# MiniWhipNext.net
KiCad netlist of a schematic drawn in EAGLE
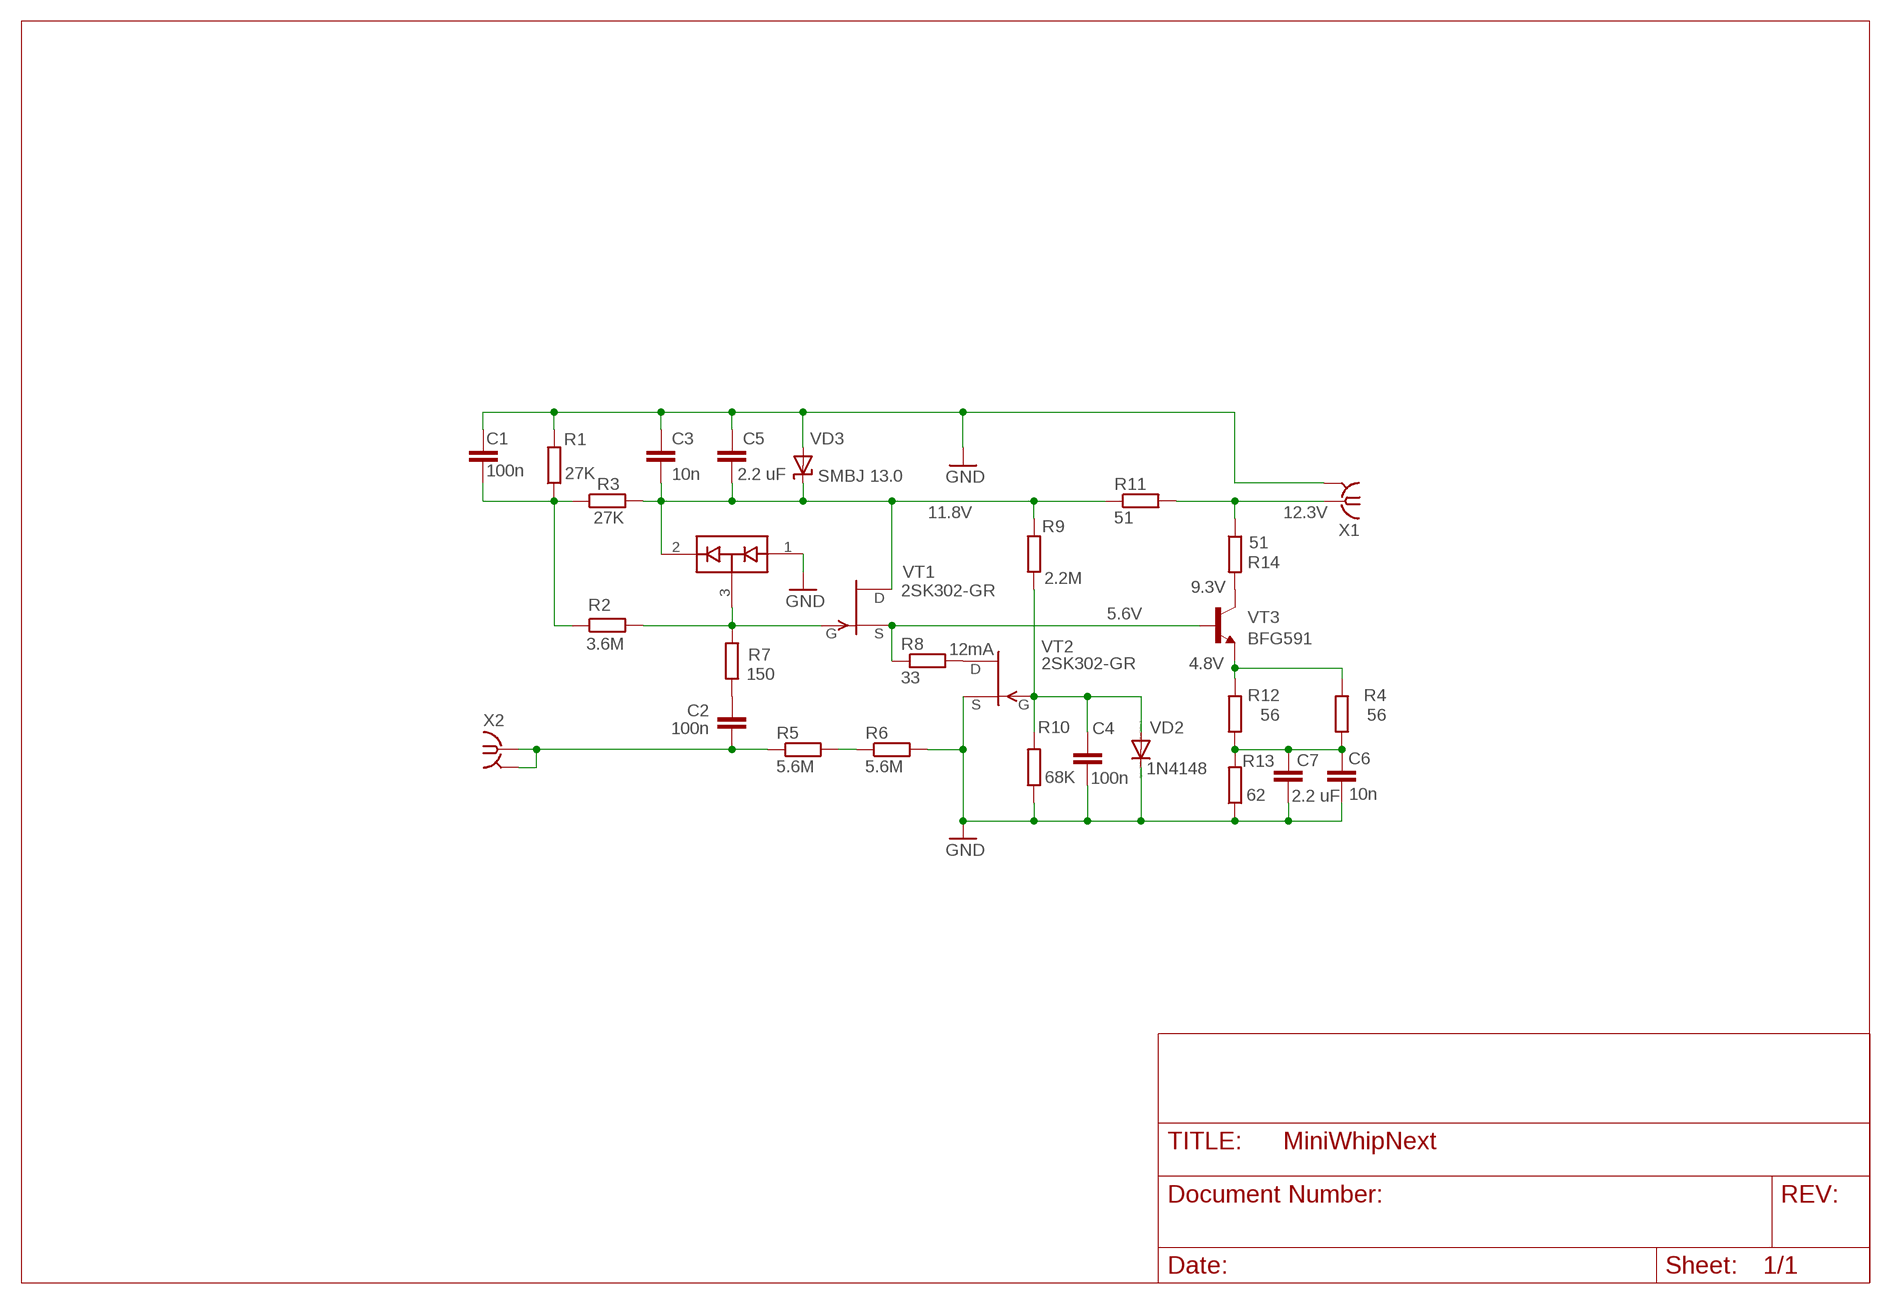
[diagram p0: schematic, sheet 1]

(export (version "E")
  (design (tool "Eeschema 10.0.6"))
  (components
    (comp (ref "C1")
      (value "100n")
      (footprint "eagle-import:C0603")
      (libsource (lib "eagle-import") (part "C-EUC0603"))
    )
    (comp (ref "C2")
      (value "100n")
      (footprint "eagle-import:C0603")
      (libsource (lib "eagle-import") (part "C-EUC0603"))
    )
    (comp (ref "C3")
      (value "10n")
      (footprint "eagle-import:C0603")
      (libsource (lib "eagle-import") (part "C-EUC0603"))
    )
    (comp (ref "C4")
      (value "100n")
      (footprint "eagle-import:C0603")
      (libsource (lib "eagle-import") (part "C-EUC0603"))
    )
    (comp (ref "C5")
      (value "2.2 uF")
      (footprint "eagle-import:C0603")
      (libsource (lib "eagle-import") (part "C-EUC0603"))
    )
    (comp (ref "C6")
      (value "10n")
      (footprint "eagle-import:C0603")
      (libsource (lib "eagle-import") (part "C-EUC0603"))
    )
    (comp (ref "C7")
      (value "2.2 uF")
      (footprint "eagle-import:C0603")
      (libsource (lib "eagle-import") (part "C-EUC0603"))
    )
    (comp (ref "R1")
      (value "27K")
      (footprint "eagle-import:R0603")
      (libsource (lib "eagle-import") (part "R-EU_R0603"))
    )
    (comp (ref "R2")
      (value "3.6M")
      (footprint "eagle-import:R0805")
      (libsource (lib "eagle-import") (part "R-EU_R0805"))
    )
    (comp (ref "R3")
      (value "27K")
      (footprint "eagle-import:R0603")
      (libsource (lib "eagle-import") (part "R-EU_R0603"))
    )
    (comp (ref "R4")
      (value "56")
      (footprint "eagle-import:R0603")
      (libsource (lib "eagle-import") (part "R-EU_R0603"))
    )
    (comp (ref "R5")
      (value "5.6M")
      (footprint "eagle-import:R0805")
      (libsource (lib "eagle-import") (part "R-EU_R0805"))
    )
    (comp (ref "R6")
      (value "5.6M")
      (footprint "eagle-import:R0805")
      (libsource (lib "eagle-import") (part "R-EU_R0805"))
    )
    (comp (ref "R7")
      (value "150")
      (footprint "eagle-import:R0805")
      (libsource (lib "eagle-import") (part "R-EU_R0805"))
    )
    (comp (ref "R8")
      (value "33")
      (footprint "eagle-import:R0805")
      (libsource (lib "eagle-import") (part "R-EU_R0805"))
    )
    (comp (ref "R9")
      (value "2.2M")
      (footprint "eagle-import:R0603")
      (libsource (lib "eagle-import") (part "R-EU_R0603"))
    )
    (comp (ref "R10")
      (value "68K")
      (footprint "eagle-import:R0603")
      (libsource (lib "eagle-import") (part "R-EU_R0603"))
    )
    (comp (ref "R11")
      (value "51")
      (footprint "eagle-import:R0603")
      (libsource (lib "eagle-import") (part "R-EU_R0603"))
    )
    (comp (ref "R12")
      (value "56")
      (footprint "eagle-import:R0603")
      (libsource (lib "eagle-import") (part "R-EU_R0603"))
    )
    (comp (ref "R13")
      (value "62")
      (footprint "eagle-import:R0603")
      (libsource (lib "eagle-import") (part "R-EU_R0603"))
    )
    (comp (ref "R14")
      (value "51")
      (footprint "eagle-import:R0603")
      (libsource (lib "eagle-import") (part "R-EU_R0603"))
    )
    (comp (ref "VD1")
      (value "BAV99")
      (footprint "eagle-import:SOT23")
      (libsource (lib "eagle-import") (part "BAV99"))
    )
    (comp (ref "VD2")
      (value "1N4148")
      (footprint "eagle-import:SOD80C")
      (libsource (lib "eagle-import") (part "DIODE-SOD80C"))
    )
    (comp (ref "VD3")
      (value "SMBJ 13.0")
      (footprint "eagle-import:SMBJ")
      (libsource (lib "eagle-import") (part "SUPPRESSOR-SMBJ"))
    )
    (comp (ref "VT1")
      (value "2SK302SOT23")
      (footprint "eagle-import:SOT23")
      (libsource (lib "eagle-import") (part "2SK302SOT23"))
    )
    (comp (ref "VT2")
      (value "2SK302SOT23")
      (footprint "eagle-import:SOT23")
      (libsource (lib "eagle-import") (part "2SK302SOT23"))
    )
    (comp (ref "VT3")
      (value "BFG591")
      (footprint "eagle-import:SOT223")
      (libsource (lib "eagle-import") (part "BFG591"))
    )
    (comp (ref "X1")
      (value "SMA-142-0701-801/806")
      (footprint "eagle-import:J502-ND-142-0701-801_806")
      (fields (field (name "MF") "JOHNSON COMPONENTS") (field (name "MPN") "142-0701-801"))
      (libsource (lib "eagle-import") (part "SMA-142-0701-801/806"))
    )
    (comp (ref "X2")
      (value "SMA-142-0701-801/806")
      (footprint "eagle-import:J502-ND-142-0701-801_806")
      (fields (field (name "MF") "JOHNSON COMPONENTS") (field (name "MPN") "142-0701-801"))
      (libsource (lib "eagle-import") (part "SMA-142-0701-801/806"))
    )
  )
  (nets
    (net (code "1") (name "GND") (class "Default")
      (node (ref "C1") (pin "1") (pinfunction "1_1") (pintype "passive"))
      (node (ref "C3") (pin "1") (pinfunction "1_1") (pintype "passive"))
      (node (ref "C4") (pin "2") (pinfunction "2_2") (pintype "passive"))
      (node (ref "C5") (pin "1") (pinfunction "1_1") (pintype "passive"))
      (node (ref "C6") (pin "2") (pinfunction "2_2") (pintype "passive"))
      (node (ref "C7") (pin "2") (pinfunction "2_2") (pintype "passive"))
      (node (ref "R1") (pin "2") (pinfunction "2_2") (pintype "passive"))
      (node (ref "R10") (pin "1") (pinfunction "1_1") (pintype "passive"))
      (node (ref "R13") (pin "1") (pinfunction "1_1") (pintype "passive"))
      (node (ref "R6") (pin "2") (pinfunction "2_2") (pintype "passive"))
      (node (ref "VD1") (pin "1") (pinfunction "A1_1") (pintype "bidirectional"))
      (node (ref "VD2") (pin "C") (pinfunction "C_C") (pintype "passive"))
      (node (ref "VD3") (pin "A") (pinfunction "A_A") (pintype "passive"))
      (node (ref "VT2") (pin "3") (pinfunction "S_3") (pintype "passive"))
      (node (ref "X1") (pin "G@1") (pinfunction "2_G@1") (pintype "passive"))
      (node (ref "X1") (pin "G@2") (pinfunction "2_G@2") (pintype "passive"))
      (node (ref "X1") (pin "G@3") (pinfunction "2_G@3") (pintype "passive"))
      (node (ref "X1") (pin "G@4") (pinfunction "2_G@4") (pintype "passive"))
    )
    (net (code "2") (name "Net-(C1-Pad2)") (class "Default")
      (node (ref "C1") (pin "2") (pinfunction "2_2") (pintype "passive"))
      (node (ref "R1") (pin "1") (pinfunction "1_1") (pintype "passive"))
      (node (ref "R2") (pin "1") (pinfunction "1_1") (pintype "passive"))
      (node (ref "R3") (pin "1") (pinfunction "1_1") (pintype "passive"))
    )
    (net (code "3") (name "Net-(C2-Pad1)") (class "Default")
      (node (ref "C2") (pin "1") (pinfunction "1_1") (pintype "passive"))
      (node (ref "R7") (pin "2") (pinfunction "2_2") (pintype "passive"))
    )
    (net (code "4") (name "Net-(C2-Pad2)") (class "Default")
      (node (ref "C2") (pin "2") (pinfunction "2_2") (pintype "passive"))
      (node (ref "R5") (pin "1") (pinfunction "1_1") (pintype "passive"))
      (node (ref "X2") (pin "1") (pinfunction "1_1") (pintype "passive"))
      (node (ref "X2") (pin "G@1") (pinfunction "2_G@1") (pintype "passive"))
      (node (ref "X2") (pin "G@2") (pinfunction "2_G@2") (pintype "passive"))
      (node (ref "X2") (pin "G@3") (pinfunction "2_G@3") (pintype "passive"))
      (node (ref "X2") (pin "G@4") (pinfunction "2_G@4") (pintype "passive"))
    )
    (net (code "5") (name "Net-(C6-Pad1)") (class "Default")
      (node (ref "C6") (pin "1") (pinfunction "1_1") (pintype "passive"))
      (node (ref "C7") (pin "1") (pinfunction "1_1") (pintype "passive"))
      (node (ref "R12") (pin "1") (pinfunction "1_1") (pintype "passive"))
      (node (ref "R13") (pin "2") (pinfunction "2_2") (pintype "passive"))
      (node (ref "R4") (pin "1") (pinfunction "1_1") (pintype "passive"))
    )
    (net (code "6") (name "Net-(R5-Pad2)") (class "Default")
      (node (ref "R5") (pin "2") (pinfunction "2_2") (pintype "passive"))
      (node (ref "R6") (pin "1") (pinfunction "1_1") (pintype "passive"))
    )
    (net (code "7") (name "Net-(R11-Pad2)") (class "Default")
      (node (ref "R11") (pin "2") (pinfunction "2_2") (pintype "passive"))
      (node (ref "R14") (pin "1") (pinfunction "1_1") (pintype "passive"))
      (node (ref "X1") (pin "1") (pinfunction "1_1") (pintype "passive"))
    )
    (net (code "8") (name "Net-(R12-Pad2)") (class "Default")
      (node (ref "R12") (pin "2") (pinfunction "2_2") (pintype "passive"))
      (node (ref "R4") (pin "2") (pinfunction "2_2") (pintype "passive"))
      (node (ref "VT3") (pin "1") (pinfunction "E_1") (pintype "passive"))
      (node (ref "VT3") (pin "3") (pinfunction "E_3") (pintype "passive"))
    )
    (net (code "9") (name "Net-(VD1-C2)") (class "Default")
      (node (ref "C3") (pin "2") (pinfunction "2_2") (pintype "passive"))
      (node (ref "C5") (pin "2") (pinfunction "2_2") (pintype "passive"))
      (node (ref "R11") (pin "1") (pinfunction "1_1") (pintype "passive"))
      (node (ref "R3") (pin "2") (pinfunction "2_2") (pintype "passive"))
      (node (ref "R9") (pin "2") (pinfunction "2_2") (pintype "passive"))
      (node (ref "VD1") (pin "2") (pinfunction "C2_2") (pintype "bidirectional"))
      (node (ref "VD3") (pin "C") (pinfunction "C_C") (pintype "passive"))
      (node (ref "VT1") (pin "1") (pinfunction "D_1") (pintype "passive"))
    )
    (net (code "10") (name "Net-(VD1-COM)") (class "Default")
      (node (ref "R2") (pin "2") (pinfunction "2_2") (pintype "passive"))
      (node (ref "R7") (pin "1") (pinfunction "1_1") (pintype "passive"))
      (node (ref "VD1") (pin "3") (pinfunction "COM_3") (pintype "bidirectional"))
      (node (ref "VT1") (pin "2") (pinfunction "G_2") (pintype "passive"))
    )
    (net (code "11") (name "Net-(VT1-S)") (class "Default")
      (node (ref "R8") (pin "1") (pinfunction "1_1") (pintype "passive"))
      (node (ref "VT1") (pin "3") (pinfunction "S_3") (pintype "passive"))
      (node (ref "VT3") (pin "2") (pinfunction "B_2") (pintype "passive"))
    )
    (net (code "12") (name "Net-(VT2-D)") (class "Default")
      (node (ref "R8") (pin "2") (pinfunction "2_2") (pintype "passive"))
      (node (ref "VT2") (pin "1") (pinfunction "D_1") (pintype "passive"))
    )
    (net (code "13") (name "Net-(VT2-G)") (class "Default")
      (node (ref "C4") (pin "1") (pinfunction "1_1") (pintype "passive"))
      (node (ref "R10") (pin "2") (pinfunction "2_2") (pintype "passive"))
      (node (ref "R9") (pin "1") (pinfunction "1_1") (pintype "passive"))
      (node (ref "VD2") (pin "A") (pinfunction "A_A") (pintype "passive"))
      (node (ref "VT2") (pin "2") (pinfunction "G_2") (pintype "passive"))
    )
    (net (code "14") (name "Net-(VT3-C)") (class "Default")
      (node (ref "R14") (pin "2") (pinfunction "2_2") (pintype "passive"))
      (node (ref "VT3") (pin "4") (pinfunction "C_4") (pintype "passive"))
    )
  )
)
